# Output.net
KiCad netlist of a schematic drawn in Altium Designer
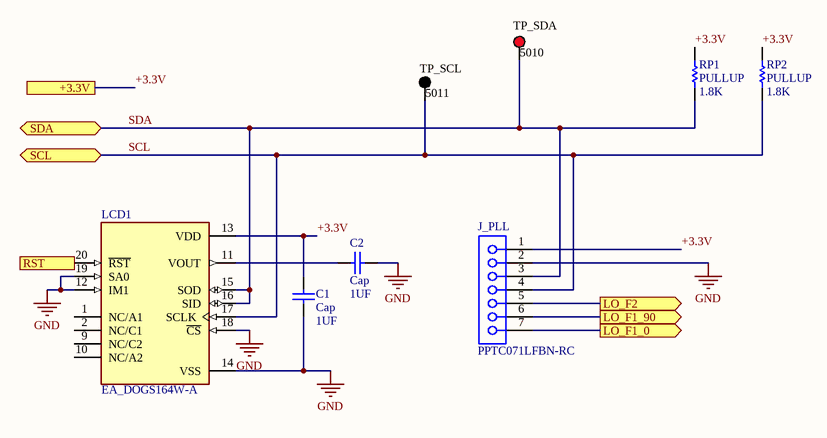
[diagram p0: Output.SchDoc]

(export (version "E")
  (design (tool "Eeschema 10.0.6"))
  (components
    (comp (ref "C1")
      (value "Cap")
      (footprint "RADIAL-0.1")
      (description "Capacitor")
      (fields
        (field (name "MANUFACTURER PART NUMBER") "ESE105M100AC3EA")
        (field (name "ALTIUM_VALUE") "1UF")
        (field (name "PUBLISHER") "Altium Limited")
      )
      (libsource (lib "ECE295-Capacitors-TH") (part "CAP ALUM 1UF 20% 100V RADIAL"))
    )
    (comp (ref "C2")
      (value "Cap")
      (footprint "RADIAL-0.1")
      (description "Capacitor")
      (fields
        (field (name "MANUFACTURER PART NUMBER") "ESE105M100AC3EA")
        (field (name "ALTIUM_VALUE") "1UF")
        (field (name "PUBLISHER") "Altium Limited")
      )
      (libsource (lib "ECE295-Capacitors-TH") (part "CAP ALUM 1UF 20% 100V RADIAL"))
    )
    (comp (ref "J_PLL")
      (value "PPTC071LFBN-RC")
      (footprint "SMTC-SSQ-107-01-X-S")
      (description "SQ Post Socket, Through-hole, Vertical, -55 to 125 degC, 2.54 mm Pitch, 7-Pin, Female, RoHS")
      (fields (field (name "PARTNUMBER") "SSQ-107-01-G-S") (field (name "MANUFACTURER") "Samtec"))
      (libsource (lib "Altium Content Vault") (part "SMTC-SSQ-107-01-X-S"))
    )
    (comp (ref "LCD1")
      (value "EA_DOGS164W-A")
      (footprint "LCD_EA_DOGS164W-A")
      (fields (field (name "MF") "Display Visions") (field (name "MP") "EA DOGS164W-A"))
      (libsource (lib "EA_DOGS164W-A") (part "EA_DOGS164W-A"))
    )
    (comp (ref "RP1")
      (value "PULLUP")
      (footprint "AXIAL-0.1-RES")
      (description "Resistor")
      (fields
        (field (name "ALTIUM_VALUE") "1.8K")
        (field (name "MANUFACTURER PART NUMBER") "CFR-25JB-52-1K8")
        (field (name "TOLERANCE") "0.05")
        (field (name "PUBLISHER") "Altium Limited")
      )
      (libsource (lib "ECE295-Resistors-TH") (part "RES 1.8K OHM 5% 1/4W AXIAL"))
    )
    (comp (ref "RP2")
      (value "PULLUP")
      (footprint "AXIAL-0.1-RES")
      (description "Resistor")
      (fields
        (field (name "ALTIUM_VALUE") "1.8K")
        (field (name "MANUFACTURER PART NUMBER") "CFR-25JB-52-1K8")
        (field (name "TOLERANCE") "0.05")
        (field (name "PUBLISHER") "Altium Limited")
      )
      (libsource (lib "ECE295-Resistors-TH") (part "RES 1.8K OHM 5% 1/4W AXIAL"))
    )
    (comp (ref "TP_SCL")
      (value "5011")
      (footprint "KSTN-5011_V")
      (description "Test Point, Black, Through Hole, RoHS, Bulk")
      (fields (field (name "MANUFACTURER") "Keystone"))
      (libsource (lib "Altium Content Vault") (part "TESTPOINT_BLACK"))
    )
    (comp (ref "TP_SDA")
      (value "5010")
      (footprint "KSTN-5010_V")
      (description "Test Point, Red, Through Hole, RoHS, Bulk")
      (fields (field (name "MANUFACTURER") "Keystone"))
      (libsource (lib "Altium Content Vault") (part "TESTPOINT_RED"))
    )
  )
  (nets
    (net (code "1") (name "/+3.3V") (class "Default")
      (node (ref "C1") (pin "2") (pinfunction "2_2") (pintype "passive"))
      (node (ref "J_PLL") (pin "1") (pinfunction "1_1") (pintype "passive"))
      (node (ref "LCD1") (pin "13") (pinfunction "VDD_13") (pintype "power_in"))
      (node (ref "RP1") (pin "2") (pinfunction "2_2") (pintype "passive"))
      (node (ref "RP2") (pin "2") (pinfunction "2_2") (pintype "passive"))
    )
    (net (code "2") (name "/LO_F1_0") (class "Default")
      (node (ref "J_PLL") (pin "7") (pinfunction "7_7") (pintype "passive"))
    )
    (net (code "3") (name "/LO_F1_90") (class "Default")
      (node (ref "J_PLL") (pin "6") (pinfunction "6_6") (pintype "passive"))
    )
    (net (code "4") (name "/LO_F2") (class "Default")
      (node (ref "J_PLL") (pin "5") (pinfunction "5_5") (pintype "passive"))
    )
    (net (code "5") (name "/RST") (class "Default")
      (node (ref "LCD1") (pin "20") (pinfunction "~{RST}_20") (pintype "input"))
    )
    (net (code "6") (name "/SCL") (class "Default")
      (node (ref "J_PLL") (pin "4") (pinfunction "4_4") (pintype "passive"))
      (node (ref "LCD1") (pin "17") (pinfunction "SCLK_17") (pintype "input"))
      (node (ref "RP2") (pin "1") (pinfunction "1_1") (pintype "passive"))
      (node (ref "TP_SCL") (pin "1") (pinfunction "1_1") (pintype "passive"))
    )
    (net (code "7") (name "/SDA") (class "Default")
      (node (ref "J_PLL") (pin "3") (pinfunction "3_3") (pintype "passive"))
      (node (ref "LCD1") (pin "15") (pinfunction "SOD_15") (pintype "bidirectional"))
      (node (ref "LCD1") (pin "16") (pinfunction "SID_16") (pintype "bidirectional"))
      (node (ref "RP1") (pin "1") (pinfunction "1_1") (pintype "passive"))
      (node (ref "TP_SDA") (pin "1") (pinfunction "1_1") (pintype "passive"))
    )
    (net (code "8") (name "GND") (class "Default")
      (node (ref "C1") (pin "1") (pinfunction "1_1") (pintype "passive"))
      (node (ref "C2") (pin "1") (pinfunction "1_1") (pintype "passive"))
      (node (ref "J_PLL") (pin "2") (pinfunction "2_2") (pintype "passive"))
      (node (ref "LCD1") (pin "12") (pinfunction "IM1_12") (pintype "input"))
      (node (ref "LCD1") (pin "14") (pinfunction "VSS_14") (pintype "power_in"))
      (node (ref "LCD1") (pin "18") (pinfunction "~{CS}_18") (pintype "input"))
      (node (ref "LCD1") (pin "19") (pinfunction "SA0_19") (pintype "input"))
    )
    (net (code "9") (name "Net-(LCD1-VOUT)") (class "Default")
      (node (ref "C2") (pin "2") (pinfunction "2_2") (pintype "passive"))
      (node (ref "LCD1") (pin "11") (pinfunction "VOUT_11") (pintype "output"))
    )
    (net (code "10") (name "unconnected-(LCD1-NC{slash}A1-Pad1)") (class "Default")
      (node (ref "LCD1") (pin "1") (pinfunction "NC/A1_1") (pintype "passive"))
    )
    (net (code "11") (name "unconnected-(LCD1-NC{slash}A2-Pad10)") (class "Default")
      (node (ref "LCD1") (pin "10") (pinfunction "NC/A2_10") (pintype "passive"))
    )
    (net (code "12") (name "unconnected-(LCD1-NC{slash}C1-Pad2)") (class "Default")
      (node (ref "LCD1") (pin "2") (pinfunction "NC/C1_2") (pintype "passive"))
    )
    (net (code "13") (name "unconnected-(LCD1-NC{slash}C2-Pad9)") (class "Default")
      (node (ref "LCD1") (pin "9") (pinfunction "NC/C2_9") (pintype "passive"))
    )
  )
)
